# Sheet1.net
KiCad netlist of a schematic drawn in Altium Designer
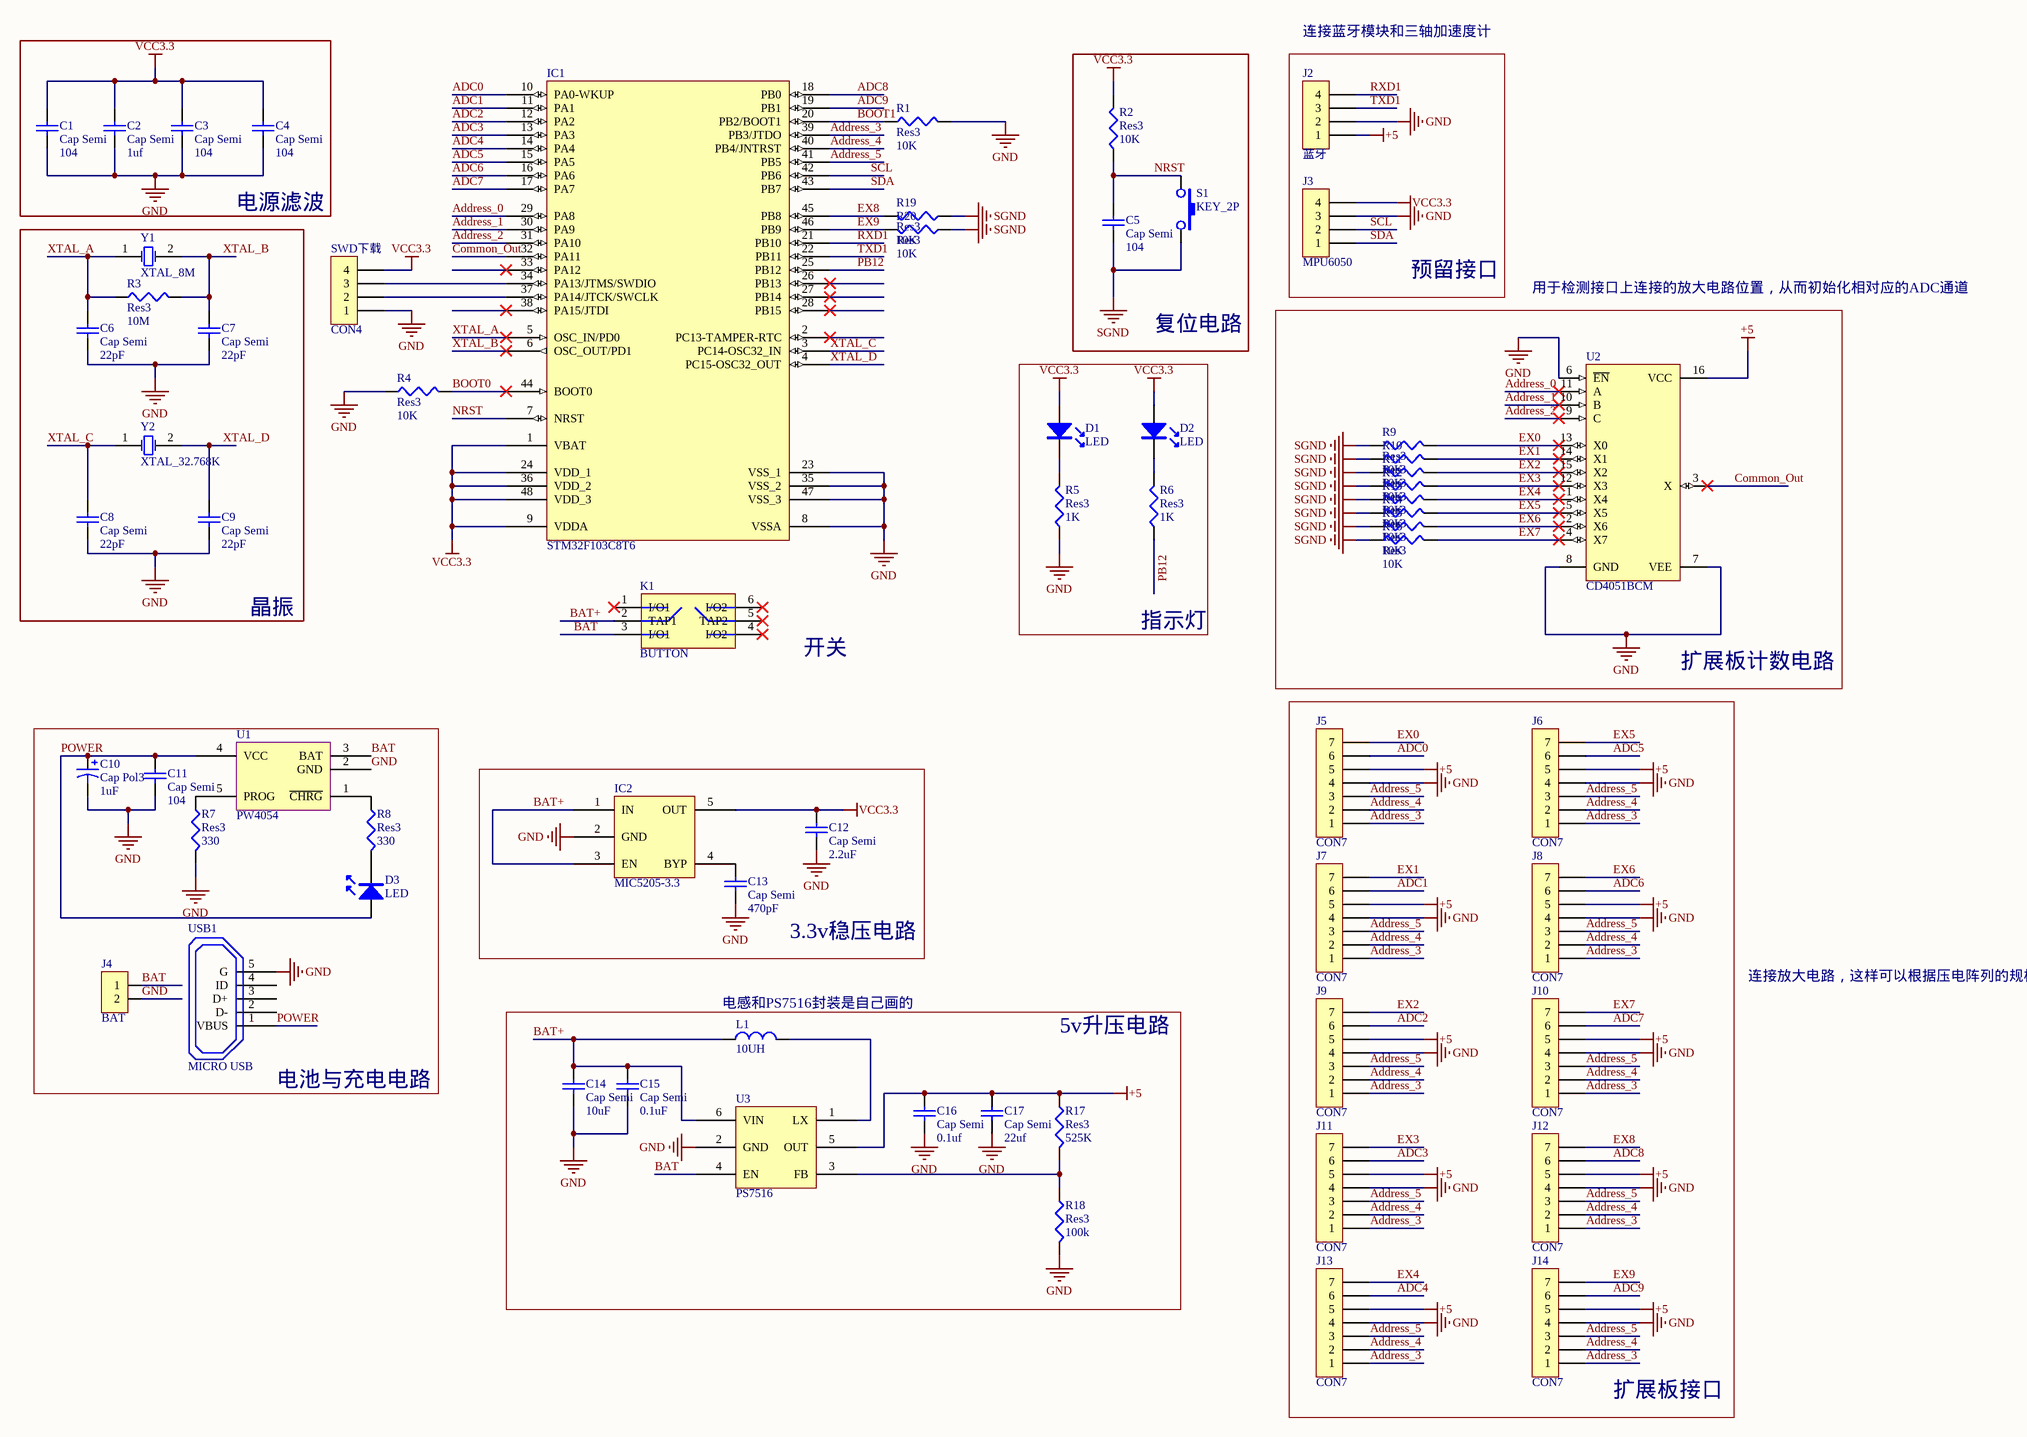
[diagram p0: Sheet1.SchDoc]

(export (version "E")
  (design (tool "Eeschema 10.0.6"))
  (components
    (comp (ref "C1")
      (value "Cap Semi")
      (footprint "6-0805_L")
      (description "Capacitor (Semiconductor SIM Model)")
      (fields (field (name "ALTIUM_VALUE") "104") (field (name "PUBLISHER") "Altium Limited"))
      (libsource (lib "Miscellaneous Devices") (part "Cap Semi"))
    )
    (comp (ref "C2")
      (value "Cap Semi")
      (footprint "6-0805_L")
      (description "Capacitor (Semiconductor SIM Model)")
      (fields (field (name "ALTIUM_VALUE") "1uf") (field (name "PUBLISHER") "Altium Limited"))
      (libsource (lib "Miscellaneous Devices") (part "Cap Semi"))
    )
    (comp (ref "C3")
      (value "Cap Semi")
      (footprint "6-0805_L")
      (description "Capacitor (Semiconductor SIM Model)")
      (fields (field (name "ALTIUM_VALUE") "104") (field (name "PUBLISHER") "Altium Limited"))
      (libsource (lib "Miscellaneous Devices") (part "Cap Semi"))
    )
    (comp (ref "C4")
      (value "Cap Semi")
      (footprint "6-0805_L")
      (description "Capacitor (Semiconductor SIM Model)")
      (fields (field (name "ALTIUM_VALUE") "104") (field (name "PUBLISHER") "Altium Limited"))
      (libsource (lib "Miscellaneous Devices") (part "Cap Semi"))
    )
    (comp (ref "C5")
      (value "Cap Semi")
      (footprint "6-0805_L")
      (description "Capacitor (Semiconductor SIM Model)")
      (fields (field (name "ALTIUM_VALUE") "104") (field (name "PUBLISHER") "Altium Limited"))
      (libsource (lib "Miscellaneous Devices") (part "Cap Semi"))
    )
    (comp (ref "C6")
      (value "Cap Semi")
      (footprint "6-0805_L")
      (description "Capacitor (Semiconductor SIM Model)")
      (fields (field (name "ALTIUM_VALUE") "22pF") (field (name "PUBLISHER") "Altium Limited"))
      (libsource (lib "Miscellaneous Devices") (part "Cap Semi"))
    )
    (comp (ref "C7")
      (value "Cap Semi")
      (footprint "6-0805_L")
      (description "Capacitor (Semiconductor SIM Model)")
      (fields (field (name "ALTIUM_VALUE") "22pF") (field (name "PUBLISHER") "Altium Limited"))
      (libsource (lib "Miscellaneous Devices") (part "Cap Semi"))
    )
    (comp (ref "C8")
      (value "Cap Semi")
      (footprint "6-0805_L")
      (description "Capacitor (Semiconductor SIM Model)")
      (fields (field (name "ALTIUM_VALUE") "22pF") (field (name "PUBLISHER") "Altium Limited"))
      (libsource (lib "Miscellaneous Devices") (part "Cap Semi"))
    )
    (comp (ref "C9")
      (value "Cap Semi")
      (footprint "6-0805_L")
      (description "Capacitor (Semiconductor SIM Model)")
      (fields (field (name "ALTIUM_VALUE") "22pF") (field (name "PUBLISHER") "Altium Limited"))
      (libsource (lib "Miscellaneous Devices") (part "Cap Semi"))
    )
    (comp (ref "C10")
      (value "Cap Pol3")
      (footprint "C0805")
      (description "Polarized Capacitor (Surface Mount)")
      (fields (field (name "ALTIUM_VALUE") "1uF") (field (name "PUBLISHER") "Altium Limited"))
      (libsource (lib "Miscellaneous Devices") (part "Cap Pol3"))
    )
    (comp (ref "C11")
      (value "Cap Semi")
      (footprint "6-0805_L")
      (description "Capacitor (Semiconductor SIM Model)")
      (fields (field (name "ALTIUM_VALUE") "104") (field (name "PUBLISHER") "Altium Limited"))
      (libsource (lib "Miscellaneous Devices") (part "Cap Semi"))
    )
    (comp (ref "C12")
      (value "Cap Semi")
      (footprint "6-0805_L")
      (description "Capacitor (Semiconductor SIM Model)")
      (fields (field (name "ALTIUM_VALUE") "2.2uF") (field (name "PUBLISHER") "Altium Limited"))
      (libsource (lib "Miscellaneous Devices") (part "Cap Semi"))
    )
    (comp (ref "C13")
      (value "Cap Semi")
      (footprint "6-0805_L")
      (description "Capacitor (Semiconductor SIM Model)")
      (fields (field (name "ALTIUM_VALUE") "470pF") (field (name "PUBLISHER") "Altium Limited"))
      (libsource (lib "Miscellaneous Devices") (part "Cap Semi"))
    )
    (comp (ref "C14")
      (value "Cap Semi")
      (footprint "6-0805_L")
      (description "Capacitor (Semiconductor SIM Model)")
      (fields (field (name "ALTIUM_VALUE") "10uF") (field (name "PUBLISHER") "Altium Limited"))
      (libsource (lib "Miscellaneous Devices") (part "Cap Semi"))
    )
    (comp (ref "C15")
      (value "Cap Semi")
      (footprint "6-0805_L")
      (description "Capacitor (Semiconductor SIM Model)")
      (fields (field (name "ALTIUM_VALUE") "0.1uF") (field (name "PUBLISHER") "Altium Limited"))
      (libsource (lib "Miscellaneous Devices") (part "Cap Semi"))
    )
    (comp (ref "C16")
      (value "Cap Semi")
      (footprint "6-0805_L")
      (description "Capacitor (Semiconductor SIM Model)")
      (fields (field (name "ALTIUM_VALUE") "0.1uf") (field (name "PUBLISHER") "Altium Limited"))
      (libsource (lib "Miscellaneous Devices") (part "Cap Semi"))
    )
    (comp (ref "C17")
      (value "Cap Semi")
      (footprint "6-0805_L")
      (description "Capacitor (Semiconductor SIM Model)")
      (fields (field (name "ALTIUM_VALUE") "22uf") (field (name "PUBLISHER") "Altium Limited"))
      (libsource (lib "Miscellaneous Devices") (part "Cap Semi"))
    )
    (comp (ref "D1") (value "LED") (footprint "6-0805_M") (libsource (lib "Component") (part "LED")))
    (comp (ref "D2") (value "LED") (footprint "6-0805_M") (libsource (lib "Component") (part "LED")))
    (comp (ref "D3") (value "LED") (footprint "6-0805_M") (libsource (lib "Component") (part "LED")))
    (comp (ref "IC1")
      (value "STM32F103C8T6")
      (footprint "LQFP48")
      (description "单片机")
      (fields (field (name "PUBLISHER") "Altium Limited"))
      (libsource (lib "Chip") (part "STM32F103C8T6"))
    )
    (comp (ref "IC2")
      (value "MIC5205-3.3")
      (footprint "SOT-23-5")
      (description "稳压")
      (libsource (lib "Chip") (part "MIC5205-3.3"))
    )
    (comp (ref "J2")
      (value "蓝牙")
      (footprint "HDR1X4")
      (description "Connector")
      (libsource (lib "杂元件库") (part "CON4"))
    )
    (comp (ref "J3")
      (value "MPU6050")
      (footprint "HDR1X4")
      (description "Connector")
      (libsource (lib "杂元件库") (part "CON4"))
    )
    (comp (ref "J4")
      (value "BAT")
      (footprint "HDR1X2")
      (description "Conjunctor")
      (libsource (lib "zj") (part "CON2"))
    )
    (comp (ref "J5")
      (value "CON7")
      (footprint "HDR1X7")
      (description "Connector")
      (libsource (lib "杂元件库") (part "CON7"))
    )
    (comp (ref "J6")
      (value "CON7")
      (footprint "HDR1X7")
      (description "Connector")
      (libsource (lib "杂元件库") (part "CON7"))
    )
    (comp (ref "J7")
      (value "CON7")
      (footprint "HDR1X7")
      (description "Connector")
      (libsource (lib "杂元件库") (part "CON7"))
    )
    (comp (ref "J8")
      (value "CON7")
      (footprint "HDR1X7")
      (description "Connector")
      (libsource (lib "杂元件库") (part "CON7"))
    )
    (comp (ref "J9")
      (value "CON7")
      (footprint "HDR1X7")
      (description "Connector")
      (libsource (lib "杂元件库") (part "CON7"))
    )
    (comp (ref "J10")
      (value "CON7")
      (footprint "HDR1X7")
      (description "Connector")
      (libsource (lib "杂元件库") (part "CON7"))
    )
    (comp (ref "J11")
      (value "CON7")
      (footprint "HDR1X7")
      (description "Connector")
      (libsource (lib "杂元件库") (part "CON7"))
    )
    (comp (ref "J12")
      (value "CON7")
      (footprint "HDR1X7")
      (description "Connector")
      (libsource (lib "杂元件库") (part "CON7"))
    )
    (comp (ref "J13")
      (value "CON7")
      (footprint "HDR1X7")
      (description "Connector")
      (libsource (lib "杂元件库") (part "CON7"))
    )
    (comp (ref "J14")
      (value "CON7")
      (footprint "HDR1X7")
      (description "Connector")
      (libsource (lib "杂元件库") (part "CON7"))
    )
    (comp (ref "K1")
      (value "BUTTON")
      (footprint "My:switch")
      (description "自锁按键")
      (libsource (lib "Component") (part "BUTTON"))
    )
    (comp (ref "L1")
      (value "10UH")
      (footprint "My:0850")
      (description "电感")
      (libsource (lib "Component") (part "Inductor"))
    )
    (comp (ref "R1")
      (value "Res3")
      (footprint "6-0805_L")
      (description "Resistor")
      (fields (field (name "ALTIUM_VALUE") "10K") (field (name "PUBLISHER") "Altium Limited"))
      (libsource (lib "Miscellaneous Devices") (part "Res3"))
    )
    (comp (ref "R2")
      (value "Res3")
      (footprint "6-0805_L")
      (description "Resistor")
      (fields (field (name "ALTIUM_VALUE") "10K") (field (name "PUBLISHER") "Altium Limited"))
      (libsource (lib "Miscellaneous Devices") (part "Res3"))
    )
    (comp (ref "R3")
      (value "Res3")
      (footprint "6-0805_L")
      (description "Resistor")
      (fields (field (name "ALTIUM_VALUE") "10M") (field (name "PUBLISHER") "Altium Limited"))
      (libsource (lib "Miscellaneous Devices") (part "Res3"))
    )
    (comp (ref "R4")
      (value "Res3")
      (footprint "6-0805_L")
      (description "Resistor")
      (fields (field (name "ALTIUM_VALUE") "10K") (field (name "PUBLISHER") "Altium Limited"))
      (libsource (lib "Miscellaneous Devices") (part "Res3"))
    )
    (comp (ref "R5")
      (value "Res3")
      (footprint "6-0805_L")
      (description "Resistor")
      (fields (field (name "ALTIUM_VALUE") "1K") (field (name "PUBLISHER") "Altium Limited"))
      (libsource (lib "Miscellaneous Devices") (part "Res3"))
    )
    (comp (ref "R6")
      (value "Res3")
      (footprint "6-0805_L")
      (description "Resistor")
      (fields (field (name "ALTIUM_VALUE") "1K") (field (name "PUBLISHER") "Altium Limited"))
      (libsource (lib "Miscellaneous Devices") (part "Res3"))
    )
    (comp (ref "R7")
      (value "Res3")
      (footprint "6-0805_L")
      (description "Resistor")
      (fields (field (name "ALTIUM_VALUE") "330") (field (name "PUBLISHER") "Altium Limited"))
      (libsource (lib "Miscellaneous Devices") (part "Res3"))
    )
    (comp (ref "R8")
      (value "Res3")
      (footprint "6-0805_L")
      (description "Resistor")
      (fields (field (name "ALTIUM_VALUE") "330") (field (name "PUBLISHER") "Altium Limited"))
      (libsource (lib "Miscellaneous Devices") (part "Res3"))
    )
    (comp (ref "R9")
      (value "Res3")
      (footprint "6-0805_L")
      (description "Resistor")
      (fields (field (name "ALTIUM_VALUE") "10K") (field (name "PUBLISHER") "Altium Limited"))
      (libsource (lib "Miscellaneous Devices") (part "Res3"))
    )
    (comp (ref "R10")
      (value "Res3")
      (footprint "6-0805_L")
      (description "Resistor")
      (fields (field (name "ALTIUM_VALUE") "10K") (field (name "PUBLISHER") "Altium Limited"))
      (libsource (lib "Miscellaneous Devices") (part "Res3"))
    )
    (comp (ref "R11")
      (value "Res3")
      (footprint "6-0805_L")
      (description "Resistor")
      (fields (field (name "ALTIUM_VALUE") "10K") (field (name "PUBLISHER") "Altium Limited"))
      (libsource (lib "Miscellaneous Devices") (part "Res3"))
    )
    (comp (ref "R12")
      (value "Res3")
      (footprint "6-0805_L")
      (description "Resistor")
      (fields (field (name "ALTIUM_VALUE") "10K") (field (name "PUBLISHER") "Altium Limited"))
      (libsource (lib "Miscellaneous Devices") (part "Res3"))
    )
    (comp (ref "R13")
      (value "Res3")
      (footprint "6-0805_L")
      (description "Resistor")
      (fields (field (name "ALTIUM_VALUE") "10K") (field (name "PUBLISHER") "Altium Limited"))
      (libsource (lib "Miscellaneous Devices") (part "Res3"))
    )
    (comp (ref "R14")
      (value "Res3")
      (footprint "6-0805_L")
      (description "Resistor")
      (fields (field (name "ALTIUM_VALUE") "10K") (field (name "PUBLISHER") "Altium Limited"))
      (libsource (lib "Miscellaneous Devices") (part "Res3"))
    )
    (comp (ref "R15")
      (value "Res3")
      (footprint "6-0805_L")
      (description "Resistor")
      (fields (field (name "ALTIUM_VALUE") "10K") (field (name "PUBLISHER") "Altium Limited"))
      (libsource (lib "Miscellaneous Devices") (part "Res3"))
    )
    (comp (ref "R16")
      (value "Res3")
      (footprint "6-0805_L")
      (description "Resistor")
      (fields (field (name "ALTIUM_VALUE") "10K") (field (name "PUBLISHER") "Altium Limited"))
      (libsource (lib "Miscellaneous Devices") (part "Res3"))
    )
    (comp (ref "R17")
      (value "Res3")
      (footprint "6-0805_L")
      (description "Resistor")
      (fields (field (name "ALTIUM_VALUE") "525K") (field (name "PUBLISHER") "Altium Limited"))
      (libsource (lib "Miscellaneous Devices") (part "Res3"))
    )
    (comp (ref "R18")
      (value "Res3")
      (footprint "6-0805_L")
      (description "Resistor")
      (fields (field (name "ALTIUM_VALUE") "100k") (field (name "PUBLISHER") "Altium Limited"))
      (libsource (lib "Miscellaneous Devices") (part "Res3"))
    )
    (comp (ref "R19")
      (value "Res3")
      (footprint "6-0805_L")
      (description "Resistor")
      (fields (field (name "ALTIUM_VALUE") "10K") (field (name "PUBLISHER") "Altium Limited"))
      (libsource (lib "Miscellaneous Devices") (part "Res3"))
    )
    (comp (ref "R20")
      (value "Res3")
      (footprint "6-0805_L")
      (description "Resistor")
      (fields (field (name "ALTIUM_VALUE") "10K") (field (name "PUBLISHER") "Altium Limited"))
      (libsource (lib "Miscellaneous Devices") (part "Res3"))
    )
    (comp (ref "S1")
      (value "KEY_2P")
      (footprint "My:SOP2")
      (description "轻触按键2P")
      (libsource (lib "Component") (part "KEY_2P"))
    )
    (comp (ref "SWD下载")
      (value "CON4")
      (footprint "HDR1X4")
      (description "连接器")
      (libsource (lib "Connector") (part "CON4"))
    )
    (comp (ref "U1") (value "PW4054") (footprint "SOT-23-CT5_L") (libsource (lib "Schlib") (part "PW4054")))
    (comp (ref "U2")
      (value "CD4051BCM")
      (footprint "M16A_N")
      (description "8-Channel Analog Multiplexer/Demultiplexer")
      (fields (field (name "PUBLISHER") "Altium Limited"))
      (libsource (lib "altium-import") (part "root_0_CD4051BCM_"))
    )
    (comp (ref "U3")
      (value "PS7516")
      (footprint "SOT23-6_M")
      (libsource (lib "Integrated_Library1") (part "PS7516"))
    )
    (comp (ref "USB1")
      (value "MICRO USB")
      (footprint "MICRO USB")
      (libsource (lib "Connector") (part "MICRO USB"))
    )
    (comp (ref "Y1")
      (value "XTAL_8M")
      (footprint "xtal")
      (description "Crystal Oscillator")
      (fields (field (name "PUBLISHER") "Altium Limited"))
      (libsource (lib "Miscellaneous Devices") (part "XTAL"))
    )
    (comp (ref "Y2")
      (value "XTAL_32.768K")
      (footprint "R38")
      (description "Crystal Oscillator")
      (fields (field (name "PUBLISHER") "Altium Limited"))
      (libsource (lib "Miscellaneous Devices") (part "XTAL"))
    )
  )
  (nets
    (net (code "1") (name "+5") (class "Default")
      (node (ref "C16") (pin "2") (pinfunction "2_2") (pintype "passive"))
      (node (ref "C17") (pin "2") (pinfunction "2_2") (pintype "passive"))
      (node (ref "J10") (pin "5") (pinfunction "5_5") (pintype "passive"))
      (node (ref "J11") (pin "5") (pinfunction "5_5") (pintype "passive"))
      (node (ref "J12") (pin "5") (pinfunction "5_5") (pintype "passive"))
      (node (ref "J13") (pin "5") (pinfunction "5_5") (pintype "passive"))
      (node (ref "J14") (pin "5") (pinfunction "5_5") (pintype "passive"))
      (node (ref "J2") (pin "1") (pinfunction "1_1") (pintype "passive"))
      (node (ref "J5") (pin "5") (pinfunction "5_5") (pintype "passive"))
      (node (ref "J6") (pin "5") (pinfunction "5_5") (pintype "passive"))
      (node (ref "J7") (pin "5") (pinfunction "5_5") (pintype "passive"))
      (node (ref "J8") (pin "5") (pinfunction "5_5") (pintype "passive"))
      (node (ref "J9") (pin "5") (pinfunction "5_5") (pintype "passive"))
      (node (ref "R17") (pin "1") (pinfunction "1_1") (pintype "passive"))
      (node (ref "U2") (pin "16") (pinfunction "VCC_16") (pintype "power_in"))
      (node (ref "U3") (pin "5") (pinfunction "OUT_5") (pintype "passive"))
    )
    (net (code "2") (name "/ADC0") (class "Default")
      (node (ref "IC1") (pin "10") (pinfunction "PA0-WKUP_10") (pintype "bidirectional"))
      (node (ref "J5") (pin "6") (pinfunction "6_6") (pintype "passive"))
    )
    (net (code "3") (name "/ADC1") (class "Default")
      (node (ref "IC1") (pin "11") (pinfunction "PA1_11") (pintype "bidirectional"))
      (node (ref "J7") (pin "6") (pinfunction "6_6") (pintype "passive"))
    )
    (net (code "4") (name "/ADC2") (class "Default")
      (node (ref "IC1") (pin "12") (pinfunction "PA2_12") (pintype "bidirectional"))
      (node (ref "J9") (pin "6") (pinfunction "6_6") (pintype "passive"))
    )
    (net (code "5") (name "/ADC3") (class "Default")
      (node (ref "IC1") (pin "13") (pinfunction "PA3_13") (pintype "bidirectional"))
      (node (ref "J11") (pin "6") (pinfunction "6_6") (pintype "passive"))
    )
    (net (code "6") (name "/ADC4") (class "Default")
      (node (ref "IC1") (pin "14") (pinfunction "PA4_14") (pintype "bidirectional"))
      (node (ref "J13") (pin "6") (pinfunction "6_6") (pintype "passive"))
    )
    (net (code "7") (name "/ADC5") (class "Default")
      (node (ref "IC1") (pin "15") (pinfunction "PA5_15") (pintype "bidirectional"))
      (node (ref "J6") (pin "6") (pinfunction "6_6") (pintype "passive"))
    )
    (net (code "8") (name "/ADC6") (class "Default")
      (node (ref "IC1") (pin "16") (pinfunction "PA6_16") (pintype "bidirectional"))
      (node (ref "J8") (pin "6") (pinfunction "6_6") (pintype "passive"))
    )
    (net (code "9") (name "/ADC7") (class "Default")
      (node (ref "IC1") (pin "17") (pinfunction "PA7_17") (pintype "bidirectional"))
      (node (ref "J10") (pin "6") (pinfunction "6_6") (pintype "passive"))
    )
    (net (code "10") (name "/ADC8") (class "Default")
      (node (ref "IC1") (pin "18") (pinfunction "PB0_18") (pintype "bidirectional"))
      (node (ref "J12") (pin "6") (pinfunction "6_6") (pintype "passive"))
    )
    (net (code "11") (name "/ADC9") (class "Default")
      (node (ref "IC1") (pin "19") (pinfunction "PB1_19") (pintype "bidirectional"))
      (node (ref "J14") (pin "6") (pinfunction "6_6") (pintype "passive"))
    )
    (net (code "12") (name "/Address_0") (class "Default")
      (node (ref "IC1") (pin "29") (pinfunction "PA8_29") (pintype "bidirectional"))
      (node (ref "U2") (pin "11") (pinfunction "A_11") (pintype "input"))
    )
    (net (code "13") (name "/Address_1") (class "Default")
      (node (ref "IC1") (pin "30") (pinfunction "PA9_30") (pintype "bidirectional"))
      (node (ref "U2") (pin "10") (pinfunction "B_10") (pintype "input"))
    )
    (net (code "14") (name "/Address_2") (class "Default")
      (node (ref "IC1") (pin "31") (pinfunction "PA10_31") (pintype "bidirectional"))
      (node (ref "U2") (pin "9") (pinfunction "C_9") (pintype "input"))
    )
    (net (code "15") (name "/Address_3") (class "Default")
      (node (ref "IC1") (pin "39") (pinfunction "PB3/JTDO_39") (pintype "bidirectional"))
      (node (ref "J10") (pin "1") (pinfunction "1_1") (pintype "passive"))
      (node (ref "J11") (pin "1") (pinfunction "1_1") (pintype "passive"))
      (node (ref "J12") (pin "1") (pinfunction "1_1") (pintype "passive"))
      (node (ref "J13") (pin "1") (pinfunction "1_1") (pintype "passive"))
      (node (ref "J14") (pin "1") (pinfunction "1_1") (pintype "passive"))
      (node (ref "J5") (pin "1") (pinfunction "1_1") (pintype "passive"))
      (node (ref "J6") (pin "1") (pinfunction "1_1") (pintype "passive"))
      (node (ref "J7") (pin "1") (pinfunction "1_1") (pintype "passive"))
      (node (ref "J8") (pin "1") (pinfunction "1_1") (pintype "passive"))
      (node (ref "J9") (pin "1") (pinfunction "1_1") (pintype "passive"))
    )
    (net (code "16") (name "/Address_4") (class "Default")
      (node (ref "IC1") (pin "40") (pinfunction "PB4/JNTRST_40") (pintype "bidirectional"))
      (node (ref "J10") (pin "2") (pinfunction "2_2") (pintype "passive"))
      (node (ref "J11") (pin "2") (pinfunction "2_2") (pintype "passive"))
      (node (ref "J12") (pin "2") (pinfunction "2_2") (pintype "passive"))
      (node (ref "J13") (pin "2") (pinfunction "2_2") (pintype "passive"))
      (node (ref "J14") (pin "2") (pinfunction "2_2") (pintype "passive"))
      (node (ref "J5") (pin "2") (pinfunction "2_2") (pintype "passive"))
      (node (ref "J6") (pin "2") (pinfunction "2_2") (pintype "passive"))
      (node (ref "J7") (pin "2") (pinfunction "2_2") (pintype "passive"))
      (node (ref "J8") (pin "2") (pinfunction "2_2") (pintype "passive"))
      (node (ref "J9") (pin "2") (pinfunction "2_2") (pintype "passive"))
    )
    (net (code "17") (name "/Address_5") (class "Default")
      (node (ref "IC1") (pin "41") (pinfunction "PB5_41") (pintype "bidirectional"))
      (node (ref "J10") (pin "3") (pinfunction "3_3") (pintype "passive"))
      (node (ref "J11") (pin "3") (pinfunction "3_3") (pintype "passive"))
      (node (ref "J12") (pin "3") (pinfunction "3_3") (pintype "passive"))
      (node (ref "J13") (pin "3") (pinfunction "3_3") (pintype "passive"))
      (node (ref "J14") (pin "3") (pinfunction "3_3") (pintype "passive"))
      (node (ref "J5") (pin "3") (pinfunction "3_3") (pintype "passive"))
      (node (ref "J6") (pin "3") (pinfunction "3_3") (pintype "passive"))
      (node (ref "J7") (pin "3") (pinfunction "3_3") (pintype "passive"))
      (node (ref "J8") (pin "3") (pinfunction "3_3") (pintype "passive"))
      (node (ref "J9") (pin "3") (pinfunction "3_3") (pintype "passive"))
    )
    (net (code "18") (name "/BAT") (class "Default")
      (node (ref "J4") (pin "1") (pinfunction "1_1") (pintype "passive"))
      (node (ref "K1") (pin "3") (pinfunction "I/O1_3") (pintype "passive"))
      (node (ref "U1") (pin "3") (pinfunction "BAT_3") (pintype "passive"))
      (node (ref "U3") (pin "4") (pinfunction "EN_4") (pintype "passive"))
    )
    (net (code "19") (name "/BAT+") (class "Default")
      (node (ref "C14") (pin "2") (pinfunction "2_2") (pintype "passive"))
      (node (ref "C15") (pin "2") (pinfunction "2_2") (pintype "passive"))
      (node (ref "IC2") (pin "1") (pinfunction "IN_1") (pintype "passive"))
      (node (ref "IC2") (pin "3") (pinfunction "EN_3") (pintype "passive"))
      (node (ref "K1") (pin "2") (pinfunction "TAP1_2") (pintype "passive"))
      (node (ref "L1") (pin "1") (pinfunction "1_1") (pintype "passive"))
      (node (ref "U3") (pin "6") (pinfunction "VIN_6") (pintype "passive"))
    )
    (net (code "20") (name "/BOOT0") (class "Default")
      (node (ref "IC1") (pin "44") (pinfunction "BOOT0_44") (pintype "input"))
      (node (ref "R4") (pin "2") (pinfunction "2_2") (pintype "passive"))
    )
    (net (code "21") (name "/BOOT1") (class "Default")
      (node (ref "IC1") (pin "20") (pinfunction "PB2/BOOT1_20") (pintype "bidirectional"))
      (node (ref "R1") (pin "1") (pinfunction "1_1") (pintype "passive"))
    )
    (net (code "22") (name "/Common_Out") (class "Default")
      (node (ref "IC1") (pin "32") (pinfunction "PA11_32") (pintype "bidirectional"))
      (node (ref "U2") (pin "3") (pinfunction "X_3") (pintype "bidirectional"))
    )
    (net (code "23") (name "/EX0") (class "Default")
      (node (ref "J5") (pin "7") (pinfunction "7_7") (pintype "passive"))
      (node (ref "R9") (pin "2") (pinfunction "2_2") (pintype "passive"))
      (node (ref "U2") (pin "13") (pinfunction "X0_13") (pintype "bidirectional"))
    )
    (net (code "24") (name "/EX1") (class "Default")
      (node (ref "J7") (pin "7") (pinfunction "7_7") (pintype "passive"))
      (node (ref "R10") (pin "2") (pinfunction "2_2") (pintype "passive"))
      (node (ref "U2") (pin "14") (pinfunction "X1_14") (pintype "bidirectional"))
    )
    (net (code "25") (name "/EX2") (class "Default")
      (node (ref "J9") (pin "7") (pinfunction "7_7") (pintype "passive"))
      (node (ref "R11") (pin "2") (pinfunction "2_2") (pintype "passive"))
      (node (ref "U2") (pin "15") (pinfunction "X2_15") (pintype "bidirectional"))
    )
    (net (code "26") (name "/EX3") (class "Default")
      (node (ref "J11") (pin "7") (pinfunction "7_7") (pintype "passive"))
      (node (ref "R12") (pin "2") (pinfunction "2_2") (pintype "passive"))
      (node (ref "U2") (pin "12") (pinfunction "X3_12") (pintype "bidirectional"))
    )
    (net (code "27") (name "/EX4") (class "Default")
      (node (ref "J13") (pin "7") (pinfunction "7_7") (pintype "passive"))
      (node (ref "R13") (pin "2") (pinfunction "2_2") (pintype "passive"))
      (node (ref "U2") (pin "1") (pinfunction "X4_1") (pintype "bidirectional"))
    )
    (net (code "28") (name "/EX5") (class "Default")
      (node (ref "J6") (pin "7") (pinfunction "7_7") (pintype "passive"))
      (node (ref "R14") (pin "2") (pinfunction "2_2") (pintype "passive"))
      (node (ref "U2") (pin "5") (pinfunction "X5_5") (pintype "bidirectional"))
    )
    (net (code "29") (name "/EX6") (class "Default")
      (node (ref "J8") (pin "7") (pinfunction "7_7") (pintype "passive"))
      (node (ref "R15") (pin "2") (pinfunction "2_2") (pintype "passive"))
      (node (ref "U2") (pin "2") (pinfunction "X6_2") (pintype "bidirectional"))
    )
    (net (code "30") (name "/EX7") (class "Default")
      (node (ref "J10") (pin "7") (pinfunction "7_7") (pintype "passive"))
      (node (ref "R16") (pin "2") (pinfunction "2_2") (pintype "passive"))
      (node (ref "U2") (pin "4") (pinfunction "X7_4") (pintype "bidirectional"))
    )
    (net (code "31") (name "/EX8") (class "Default")
      (node (ref "IC1") (pin "45") (pinfunction "PB8_45") (pintype "bidirectional"))
      (node (ref "J12") (pin "7") (pinfunction "7_7") (pintype "passive"))
      (node (ref "R19") (pin "2") (pinfunction "2_2") (pintype "passive"))
    )
    (net (code "32") (name "/EX9") (class "Default")
      (node (ref "IC1") (pin "46") (pinfunction "PB9_46") (pintype "bidirectional"))
      (node (ref "J14") (pin "7") (pinfunction "7_7") (pintype "passive"))
      (node (ref "R20") (pin "2") (pinfunction "2_2") (pintype "passive"))
    )
    (net (code "33") (name "/NRST") (class "Default")
      (node (ref "C5") (pin "2") (pinfunction "2_2") (pintype "passive"))
      (node (ref "IC1") (pin "7") (pinfunction "NRST_7") (pintype "bidirectional"))
      (node (ref "R2") (pin "1") (pinfunction "1_1") (pintype "passive"))
      (node (ref "S1") (pin "1") (pinfunction "1_1") (pintype "passive"))
    )
    (net (code "34") (name "/PB12") (class "Default")
      (node (ref "IC1") (pin "25") (pinfunction "PB12_25") (pintype "bidirectional"))
      (node (ref "R6") (pin "1") (pinfunction "1_1") (pintype "passive"))
    )
    (net (code "35") (name "/POWER") (class "Default")
      (node (ref "C10") (pin "1") (pinfunction "1_1") (pintype "passive"))
      (node (ref "C11") (pin "2") (pinfunction "2_2") (pintype "passive"))
      (node (ref "D3") (pin "1") (pinfunction "1_1") (pintype "passive"))
      (node (ref "U1") (pin "4") (pinfunction "VCC_4") (pintype "passive"))
      (node (ref "USB1") (pin "1") (pinfunction "VBUS_1") (pintype "passive"))
    )
    (net (code "36") (name "/RXD1") (class "Default")
      (node (ref "IC1") (pin "21") (pinfunction "PB10_21") (pintype "bidirectional"))
      (node (ref "J2") (pin "4") (pinfunction "4_4") (pintype "passive"))
    )
    (net (code "37") (name "/SCL") (class "Default")
      (node (ref "IC1") (pin "42") (pinfunction "PB6_42") (pintype "bidirectional"))
      (node (ref "J3") (pin "2") (pinfunction "2_2") (pintype "passive"))
    )
    (net (code "38") (name "/SDA") (class "Default")
      (node (ref "IC1") (pin "43") (pinfunction "PB7_43") (pintype "bidirectional"))
      (node (ref "J3") (pin "1") (pinfunction "1_1") (pintype "passive"))
    )
    (net (code "39") (name "/TXD1") (class "Default")
      (node (ref "IC1") (pin "22") (pinfunction "PB11_22") (pintype "bidirectional"))
      (node (ref "J2") (pin "3") (pinfunction "3_3") (pintype "passive"))
    )
    (net (code "40") (name "/XTAL_A") (class "Default")
      (node (ref "C6") (pin "2") (pinfunction "2_2") (pintype "passive"))
      (node (ref "IC1") (pin "5") (pinfunction "OSC_IN/PD0_5") (pintype "input"))
      (node (ref "R3") (pin "1") (pinfunction "1_1") (pintype "passive"))
      (node (ref "Y1") (pin "1") (pinfunction "OSC1_1") (pintype "passive"))
    )
    (net (code "41") (name "/XTAL_B") (class "Default")
      (node (ref "C7") (pin "2") (pinfunction "2_2") (pintype "passive"))
      (node (ref "IC1") (pin "6") (pinfunction "OSC_OUT/PD1_6") (pintype "output"))
      (node (ref "R3") (pin "2") (pinfunction "2_2") (pintype "passive"))
      (node (ref "Y1") (pin "2") (pinfunction "OSC2_2") (pintype "passive"))
    )
    (net (code "42") (name "/XTAL_C") (class "Default")
      (node (ref "C8") (pin "2") (pinfunction "2_2") (pintype "passive"))
      (node (ref "IC1") (pin "3") (pinfunction "PC14-OSC32_IN_3") (pintype "bidirectional"))
      (node (ref "Y2") (pin "1") (pinfunction "OSC1_1") (pintype "passive"))
    )
    (net (code "43") (name "/XTAL_D") (class "Default")
      (node (ref "C9") (pin "2") (pinfunction "2_2") (pintype "passive"))
      (node (ref "IC1") (pin "4") (pinfunction "PC15-OSC32_OUT_4") (pintype "bidirectional"))
      (node (ref "Y2") (pin "2") (pinfunction "OSC2_2") (pintype "passive"))
    )
    (net (code "44") (name "GND") (class "Default")
      (node (ref "C1") (pin "1") (pinfunction "1_1") (pintype "passive"))
      (node (ref "C10") (pin "2") (pinfunction "2_2") (pintype "passive"))
      (node (ref "C11") (pin "1") (pinfunction "1_1") (pintype "passive"))
      (node (ref "C12") (pin "1") (pinfunction "1_1") (pintype "passive"))
      (node (ref "C13") (pin "1") (pinfunction "1_1") (pintype "passive"))
      (node (ref "C14") (pin "1") (pinfunction "1_1") (pintype "passive"))
      (node (ref "C15") (pin "1") (pinfunction "1_1") (pintype "passive"))
      (node (ref "C16") (pin "1") (pinfunction "1_1") (pintype "passive"))
      (node (ref "C17") (pin "1") (pinfunction "1_1") (pintype "passive"))
      (node (ref "C2") (pin "1") (pinfunction "1_1") (pintype "passive"))
      (node (ref "C3") (pin "1") (pinfunction "1_1") (pintype "passive"))
      (node (ref "C4") (pin "1") (pinfunction "1_1") (pintype "passive"))
      (node (ref "C6") (pin "1") (pinfunction "1_1") (pintype "passive"))
      (node (ref "C7") (pin "1") (pinfunction "1_1") (pintype "passive"))
      (node (ref "C8") (pin "1") (pinfunction "1_1") (pintype "passive"))
      (node (ref "C9") (pin "1") (pinfunction "1_1") (pintype "passive"))
      (node (ref "IC1") (pin "23") (pinfunction "VSS_1_23") (pintype "power_in"))
      (node (ref "IC1") (pin "35") (pinfunction "VSS_2_35") (pintype "power_in"))
      (node (ref "IC1") (pin "47") (pinfunction "VSS_3_47") (pintype "power_in"))
      (node (ref "IC1") (pin "8") (pinfunction "VSSA_8") (pintype "power_in"))
      (node (ref "IC2") (pin "2") (pinfunction "GND_2") (pintype "passive"))
      (node (ref "J10") (pin "4") (pinfunction "4_4") (pintype "passive"))
      (node (ref "J11") (pin "4") (pinfunction "4_4") (pintype "passive"))
      (node (ref "J12") (pin "4") (pinfunction "4_4") (pintype "passive"))
      (node (ref "J13") (pin "4") (pinfunction "4_4") (pintype "passive"))
      (node (ref "J14") (pin "4") (pinfunction "4_4") (pintype "passive"))
      (node (ref "J2") (pin "2") (pinfunction "2_2") (pintype "passive"))
      (node (ref "J3") (pin "3") (pinfunction "3_3") (pintype "passive"))
      (node (ref "J4") (pin "2") (pinfunction "2_2") (pintype "passive"))
      (node (ref "J5") (pin "4") (pinfunction "4_4") (pintype "passive"))
      (node (ref "J6") (pin "4") (pinfunction "4_4") (pintype "passive"))
      (node (ref "J7") (pin "4") (pinfunction "4_4") (pintype "passive"))
      (node (ref "J8") (pin "4") (pinfunction "4_4") (pintype "passive"))
      (node (ref "J9") (pin "4") (pinfunction "4_4") (pintype "passive"))
      (node (ref "R1") (pin "2") (pinfunction "2_2") (pintype "passive"))
      (node (ref "R18") (pin "2") (pinfunction "2_2") (pintype "passive"))
      (node (ref "R4") (pin "1") (pinfunction "1_1") (pintype "passive"))
      (node (ref "R5") (pin "1") (pinfunction "1_1") (pintype "passive"))
      (node (ref "R7") (pin "2") (pinfunction "2_2") (pintype "passive"))
      (node (ref "SWD下载") (pin "1") (pinfunction "1_1") (pintype "passive"))
      (node (ref "U1") (pin "2") (pinfunction "GND_2") (pintype "passive"))
      (node (ref "U2") (pin "6") (pinfunction "~{EN}_6") (pintype "input"))
      (node (ref "U2") (pin "7") (pinfunction "VEE_7") (pintype "power_in"))
      (node (ref "U2") (pin "8") (pinfunction "GND_8") (pintype "power_in"))
      (node (ref "U3") (pin "2") (pinfunction "GND_2") (pintype "passive"))
      (node (ref "USB1") (pin "5") (pinfunction "G_5") (pintype "passive"))
    )
    (net (code "45") (name "Net-(D1-Pad2)") (class "Default")
      (node (ref "D1") (pin "2") (pinfunction "2_2") (pintype "passive"))
      (node (ref "R5") (pin "2") (pinfunction "2_2") (pintype "passive"))
    )
    (net (code "46") (name "Net-(D2-Pad2)") (class "Default")
      (node (ref "D2") (pin "2") (pinfunction "2_2") (pintype "passive"))
      (node (ref "R6") (pin "2") (pinfunction "2_2") (pintype "passive"))
    )
    (net (code "47") (name "Net-(D3-Pad2)") (class "Default")
      (node (ref "D3") (pin "2") (pinfunction "2_2") (pintype "passive"))
      (node (ref "R8") (pin "2") (pinfunction "2_2") (pintype "passive"))
    )
    (net (code "48") (name "Net-(IC1-PA13{slash}JTMS{slash}SWDIO)") (class "Default")
      (node (ref "IC1") (pin "34") (pinfunction "PA13/JTMS/SWDIO_34") (pintype "bidirectional"))
      (node (ref "SWD下载") (pin "3") (pinfunction "3_3") (pintype "passive"))
    )
    (net (code "49") (name "Net-(IC1-PA14{slash}JTCK{slash}SWCLK)") (class "Default")
      (node (ref "IC1") (pin "37") (pinfunction "PA14/JTCK/SWCLK_37") (pintype "bidirectional"))
      (node (ref "SWD下载") (pin "2") (pinfunction "2_2") (pintype "passive"))
    )
    (net (code "50") (name "Net-(IC2-BYP)") (class "Default")
      (node (ref "C13") (pin "2") (pinfunction "2_2") (pintype "passive"))
      (node (ref "IC2") (pin "4") (pinfunction "BYP_4") (pintype "passive"))
    )
    (net (code "51") (name "Net-(U1-PROG)") (class "Default")
      (node (ref "R7") (pin "1") (pinfunction "1_1") (pintype "passive"))
      (node (ref "U1") (pin "5") (pinfunction "PROG_5") (pintype "passive"))
    )
    (net (code "52") (name "Net-(U1-~{CHRG})") (class "Default")
      (node (ref "R8") (pin "1") (pinfunction "1_1") (pintype "passive"))
      (node (ref "U1") (pin "1") (pinfunction "~{CHRG}_1") (pintype "passive"))
    )
    (net (code "53") (name "Net-(U3-FB)") (class "Default")
      (node (ref "R17") (pin "2") (pinfunction "2_2") (pintype "passive"))
      (node (ref "R18") (pin "1") (pinfunction "1_1") (pintype "passive"))
      (node (ref "U3") (pin "3") (pinfunction "FB_3") (pintype "passive"))
    )
    (net (code "54") (name "Net-(U3-LX)") (class "Default")
      (node (ref "L1") (pin "2") (pinfunction "2_2") (pintype "passive"))
      (node (ref "U3") (pin "1") (pinfunction "LX_1") (pintype "passive"))
    )
    (net (code "55") (name "SGND") (class "Default")
      (node (ref "C5") (pin "1") (pinfunction "1_1") (pintype "passive"))
      (node (ref "R10") (pin "1") (pinfunction "1_1") (pintype "passive"))
      (node (ref "R11") (pin "1") (pinfunction "1_1") (pintype "passive"))
      (node (ref "R12") (pin "1") (pinfunction "1_1") (pintype "passive"))
      (node (ref "R13") (pin "1") (pinfunction "1_1") (pintype "passive"))
      (node (ref "R14") (pin "1") (pinfunction "1_1") (pintype "passive"))
      (node (ref "R15") (pin "1") (pinfunction "1_1") (pintype "passive"))
      (node (ref "R16") (pin "1") (pinfunction "1_1") (pintype "passive"))
      (node (ref "R19") (pin "1") (pinfunction "1_1") (pintype "passive"))
      (node (ref "R20") (pin "1") (pinfunction "1_1") (pintype "passive"))
      (node (ref "R9") (pin "1") (pinfunction "1_1") (pintype "passive"))
      (node (ref "S1") (pin "2") (pinfunction "2_2") (pintype "passive"))
    )
    (net (code "56") (name "VCC3.3") (class "Default")
      (node (ref "C1") (pin "2") (pinfunction "2_2") (pintype "passive"))
      (node (ref "C12") (pin "2") (pinfunction "2_2") (pintype "passive"))
      (node (ref "C2") (pin "2") (pinfunction "2_2") (pintype "passive"))
      (node (ref "C3") (pin "2") (pinfunction "2_2") (pintype "passive"))
      (node (ref "C4") (pin "2") (pinfunction "2_2") (pintype "passive"))
      (node (ref "D1") (pin "1") (pinfunction "1_1") (pintype "passive"))
      (node (ref "D2") (pin "1") (pinfunction "1_1") (pintype "passive"))
      (node (ref "IC1") (pin "1") (pinfunction "VBAT_1") (pintype "power_in"))
      (node (ref "IC1") (pin "24") (pinfunction "VDD_1_24") (pintype "power_in"))
      (node (ref "IC1") (pin "36") (pinfunction "VDD_2_36") (pintype "power_in"))
      (node (ref "IC1") (pin "48") (pinfunction "VDD_3_48") (pintype "power_in"))
      (node (ref "IC1") (pin "9") (pinfunction "VDDA_9") (pintype "power_in"))
      (node (ref "IC2") (pin "5") (pinfunction "OUT_5") (pintype "passive"))
      (node (ref "J3") (pin "4") (pinfunction "4_4") (pintype "passive"))
      (node (ref "R2") (pin "2") (pinfunction "2_2") (pintype "passive"))
      (node (ref "SWD下载") (pin "4") (pinfunction "4_4") (pintype "passive"))
    )
    (net (code "57") (name "unconnected-(IC1-PA12-Pad33)") (class "Default")
      (node (ref "IC1") (pin "33") (pinfunction "PA12_33") (pintype "bidirectional+no_connect"))
    )
    (net (code "58") (name "unconnected-(IC1-PA15{slash}JTDI-Pad38)") (class "Default")
      (node (ref "IC1") (pin "38") (pinfunction "PA15/JTDI_38") (pintype "bidirectional+no_connect"))
    )
    (net (code "59") (name "unconnected-(IC1-PB13-Pad26)") (class "Default")
      (node (ref "IC1") (pin "26") (pinfunction "PB13_26") (pintype "bidirectional+no_connect"))
    )
    (net (code "60") (name "unconnected-(IC1-PB14-Pad27)") (class "Default")
      (node (ref "IC1") (pin "27") (pinfunction "PB14_27") (pintype "bidirectional+no_connect"))
    )
    (net (code "61") (name "unconnected-(IC1-PB15-Pad28)") (class "Default")
      (node (ref "IC1") (pin "28") (pinfunction "PB15_28") (pintype "bidirectional+no_connect"))
    )
    (net (code "62") (name "unconnected-(IC1-PC13-TAMPER-RTC-Pad2)") (class "Default")
      (node (ref "IC1") (pin "2") (pinfunction "PC13-TAMPER-RTC_2") (pintype "bidirectional+no_connect"))
    )
    (net (code "63") (name "unconnected-(K1-I{slash}O1-Pad1)") (class "Default")
      (node (ref "K1") (pin "1") (pinfunction "I/O1_1") (pintype "passive+no_connect"))
    )
    (net (code "64") (name "unconnected-(K1-I{slash}O2-Pad4)") (class "Default")
      (node (ref "K1") (pin "4") (pinfunction "I/O2_4") (pintype "passive+no_connect"))
    )
    (net (code "65") (name "unconnected-(K1-I{slash}O2-Pad6)") (class "Default")
      (node (ref "K1") (pin "6") (pinfunction "I/O2_6") (pintype "passive+no_connect"))
    )
    (net (code "66") (name "unconnected-(K1-TAP2-Pad5)") (class "Default")
      (node (ref "K1") (pin "5") (pinfunction "TAP2_5") (pintype "passive+no_connect"))
    )
    (net (code "67") (name "unconnected-(USB1-D+-Pad3)") (class "Default")
      (node (ref "USB1") (pin "3") (pinfunction "D+_3") (pintype "passive"))
    )
    (net (code "68") (name "unconnected-(USB1-D--Pad2)") (class "Default")
      (node (ref "USB1") (pin "2") (pinfunction "D-_2") (pintype "passive"))
    )
    (net (code "69") (name "unconnected-(USB1-ID-Pad4)") (class "Default")
      (node (ref "USB1") (pin "4") (pinfunction "ID_4") (pintype "passive"))
    )
  )
)
